# ProxSensorType2_Transmit.net
KiCad netlist of a schematic drawn in Altium Designer
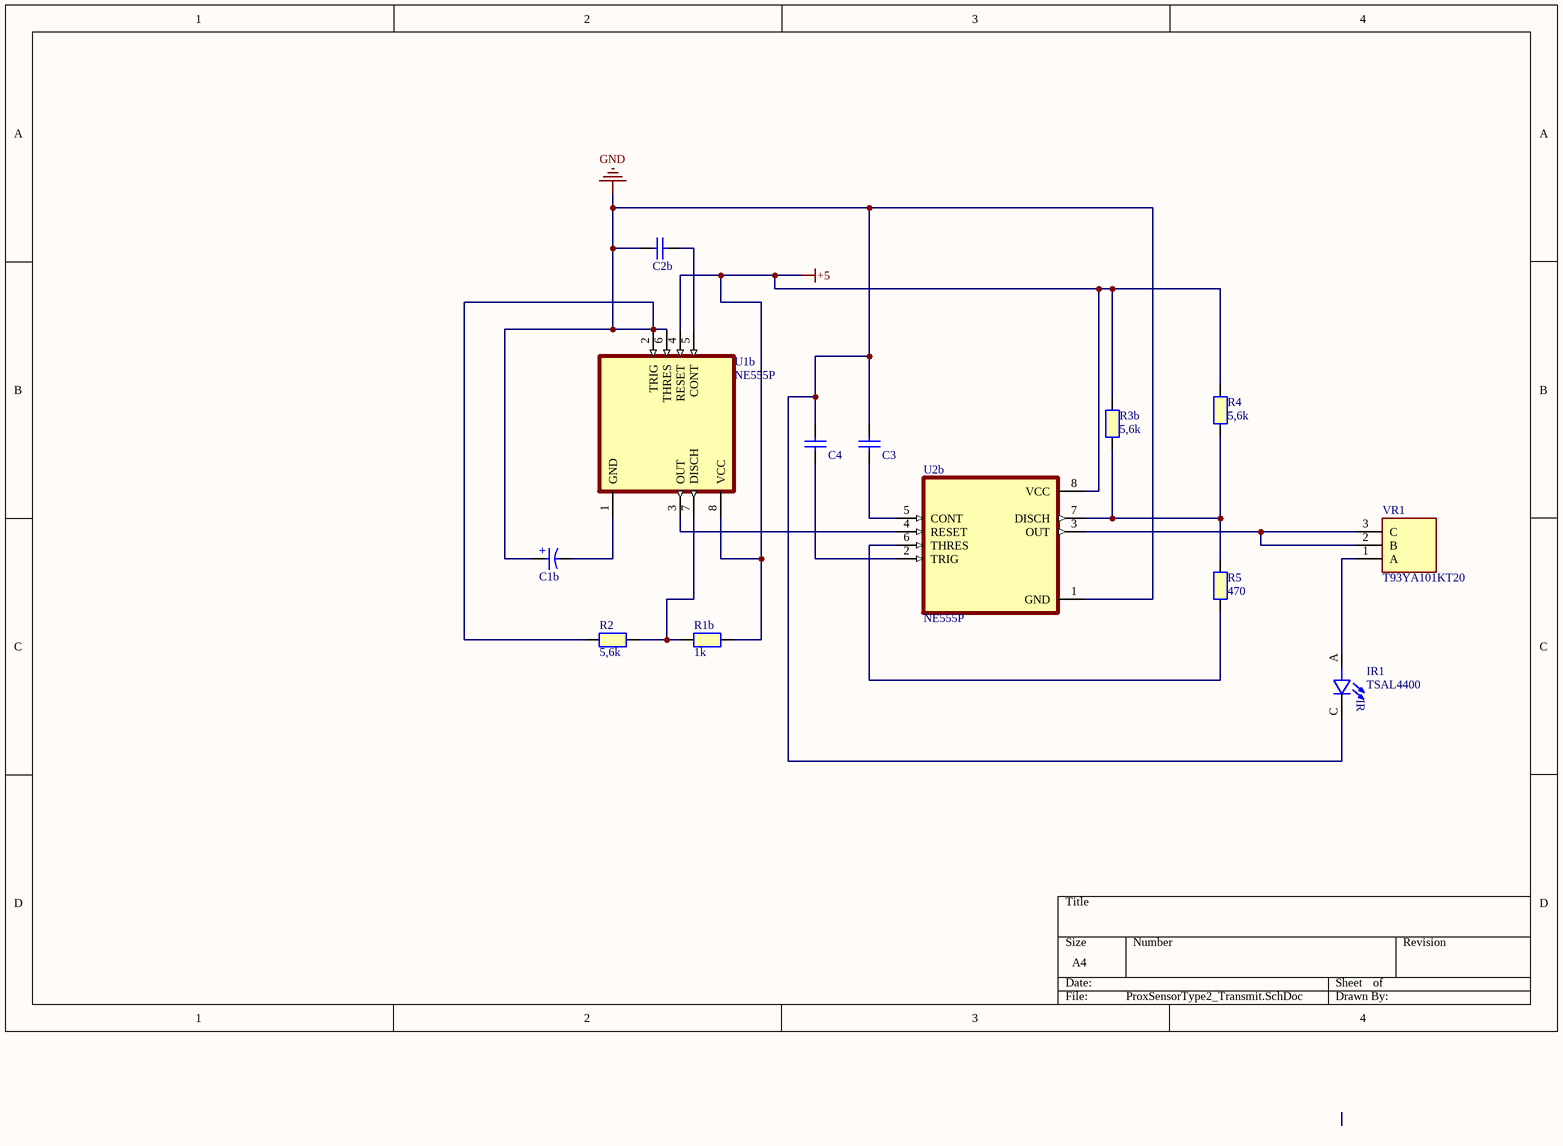
[diagram p0: ProxSensorType2_Transmit.SchDoc]

(export (version "E")
  (design (tool "Eeschema 10.0.6"))
  (components
    (comp (ref "C1b")
      (value "1µF")
      (footprint "WCAP-ATG8_D5H11")
      (description "WCAP-ATG8 Aluminum Electrolytic Capacitor, Radial, THT, D5 x H11mm, 100µF, 10V")
      (fields
        (field (name "MANUFACTURER PART NUMBER") "860010272005")
        (field (name "MANUFACTURER") "Wurth Elektronik")
      )
      (libsource (lib "Sensor_1") (part "860010272005"))
    )
    (comp (ref "C2b")
      (value "0,01uF")
      (footprint "WCAP-CSGP_0805_L2W1.25H0.8_Wave")
      (description "WCAP-CSGP Multilayer Ceramic Chip Capacitor, General Purpose, size 0201, NP0 Class I, 22pF, 25VDC")
      (fields
        (field (name "MANUFACTURER PART NUMBER") "885012004008")
        (field (name "MANUFACTURER") "Wurth Elektronik")
      )
      (libsource (lib "Sensor_1") (part "885012004008"))
    )
    (comp (ref "C3")
      (value "0,01uF")
      (footprint "WCAP-CSGP_0805_L2W1.25H0.8_Wave")
      (description "WCAP-CSGP Multilayer Ceramic Chip Capacitor, General Purpose, size 0201, NP0 Class I, 22pF, 25VDC")
      (fields
        (field (name "MANUFACTURER PART NUMBER") "885012004008")
        (field (name "MANUFACTURER") "Wurth Elektronik")
      )
      (libsource (lib "Sensor_1") (part "885012004008"))
    )
    (comp (ref "C4")
      (value "0,01uF")
      (footprint "WCAP-CSGP_0805_L2W1.25H0.8_Wave")
      (description "WCAP-CSGP Multilayer Ceramic Chip Capacitor, General Purpose, size 0201, NP0 Class I, 22pF, 25VDC")
      (fields
        (field (name "MANUFACTURER PART NUMBER") "885012004008")
        (field (name "MANUFACTURER") "Wurth Elektronik")
      )
      (libsource (lib "Sensor_1") (part "885012004008"))
    )
    (comp (ref "IR1")
      (value "TSAL4400")
      (footprint "Sensor_1:LEDRD254W45D335H610")
      (description "Infrared Emitter 940nm 36mW/sr Circular Top Mount 2-Pin T-1 Bulk")
      (fields (field (name "MF") "Vishay Semiconductor"))
      (libsource (lib "Sensor_1") (part "TSAL4400"))
    )
    (comp (ref "R1b")
      (value "1k")
      (footprint "RESC2012X50N")
      (description "4,7k Resistor 0805")
      (fields (field (name "PART NUMBER") "TNPW080510K0BETA") (field (name "MANUFACTURER") "Vishay Dale"))
      (libsource (lib "") (part "RESISTOR 0805_1"))
    )
    (comp (ref "R2")
      (value "5,6k")
      (footprint "RESC2012X50N")
      (description "4,7k Resistor 0805")
      (fields (field (name "PART NUMBER") "TNPW080510K0BETA") (field (name "MANUFACTURER") "Vishay Dale"))
      (libsource (lib "") (part "RESISTOR 0805_1"))
    )
    (comp (ref "R3b")
      (value "5,6k")
      (footprint "RESC2012X50N")
      (description "4,7k Resistor 0805")
      (fields (field (name "PART NUMBER") "TNPW080510K0BETA") (field (name "MANUFACTURER") "Vishay Dale"))
      (libsource (lib "Sensor_1") (part "RESISTOR 0805"))
    )
    (comp (ref "R4")
      (value "5,6k")
      (footprint "RESC2012X50N")
      (description "4,7k Resistor 0805")
      (fields (field (name "PART NUMBER") "TNPW080510K0BETA") (field (name "MANUFACTURER") "Vishay Dale"))
      (libsource (lib "Sensor_1") (part "RESISTOR 0805"))
    )
    (comp (ref "R5")
      (value "470")
      (footprint "RESC2012X50N")
      (description "4,7k Resistor 0805")
      (fields (field (name "PART NUMBER") "TNPW080510K0BETA") (field (name "MANUFACTURER") "Vishay Dale"))
      (libsource (lib "Sensor_1") (part "RESISTOR 0805"))
    )
    (comp (ref "U1b")
      (value "NE555P")
      (footprint "Sensor_1:DIP794W45P254L959H508Q8")
      (libsource (lib "Sensor_1") (part "NE555P"))
    )
    (comp (ref "U2b")
      (value "NE555P")
      (footprint "Sensor_1:DIP794W45P254L959H508Q8")
      (libsource (lib "") (part "NE555P_1"))
    )
    (comp (ref "VR1")
      (value "T93YA101KT20")
      (footprint "T93YA5K10")
      (description "100, Through Hole Trimmer Potentiometer 0.5W Top Adjust Vishay, T93")
      (fields (field (name "MOUSER PART NUMBER") "72-T93YA-100"))
      (libsource (lib "Sensor_1") (part "T93YA101KT20"))
    )
  )
  (nets
    (net (code "1") (name "+5") (class "Default")
      (node (ref "R1b") (pin "2") (pinfunction "2_2") (pintype "passive"))
      (node (ref "R3b") (pin "2") (pinfunction "2_2") (pintype "passive"))
      (node (ref "R4") (pin "2") (pinfunction "2_2") (pintype "passive"))
      (node (ref "U1b") (pin "4") (pinfunction "RESET_4") (pintype "input"))
      (node (ref "U1b") (pin "8") (pinfunction "VCC_8") (pintype "power_in"))
      (node (ref "U2b") (pin "8") (pinfunction "VCC_8") (pintype "power_in"))
    )
    (net (code "2") (name "GND") (class "Default")
      (node (ref "C1b") (pin "1") (pinfunction "P_1") (pintype "passive"))
      (node (ref "C2b") (pin "1") (pinfunction "1_1") (pintype "passive"))
      (node (ref "C3") (pin "2") (pinfunction "2_2") (pintype "passive"))
      (node (ref "C4") (pin "2") (pinfunction "2_2") (pintype "passive"))
      (node (ref "IR1") (pin "C") (pinfunction "C_C") (pintype "passive"))
      (node (ref "R2") (pin "1") (pinfunction "1_1") (pintype "passive"))
      (node (ref "U1b") (pin "2") (pinfunction "TRIG_2") (pintype "input"))
      (node (ref "U1b") (pin "6") (pinfunction "THRES_6") (pintype "input"))
      (node (ref "U2b") (pin "1") (pinfunction "GND_1") (pintype "power_in"))
    )
    (net (code "3") (name "Net-(C1b-N)") (class "Default")
      (node (ref "C1b") (pin "2") (pinfunction "N_2") (pintype "passive"))
      (node (ref "U1b") (pin "1") (pinfunction "GND_1") (pintype "power_in"))
    )
    (net (code "4") (name "Net-(U1b-CONT)") (class "Default")
      (node (ref "C2b") (pin "2") (pinfunction "2_2") (pintype "passive"))
      (node (ref "U1b") (pin "5") (pinfunction "CONT_5") (pintype "input"))
    )
    (net (code "5") (name "Net-(U1b-DISCH)") (class "Default")
      (node (ref "R1b") (pin "1") (pinfunction "1_1") (pintype "passive"))
      (node (ref "R2") (pin "2") (pinfunction "2_2") (pintype "passive"))
      (node (ref "U1b") (pin "7") (pinfunction "DISCH_7") (pintype "output"))
    )
    (net (code "6") (name "Net-(U1b-OUT)") (class "Default")
      (node (ref "U1b") (pin "3") (pinfunction "OUT_3") (pintype "output"))
      (node (ref "U2b") (pin "4") (pinfunction "RESET_4") (pintype "input"))
    )
    (net (code "7") (name "Net-(U2b-CONT)") (class "Default")
      (node (ref "C3") (pin "1") (pinfunction "1_1") (pintype "passive"))
      (node (ref "U2b") (pin "5") (pinfunction "CONT_5") (pintype "input"))
    )
    (net (code "8") (name "Net-(U2b-DISCH)") (class "Default")
      (node (ref "R3b") (pin "1") (pinfunction "1_1") (pintype "passive"))
      (node (ref "R4") (pin "1") (pinfunction "1_1") (pintype "passive"))
      (node (ref "R5") (pin "2") (pinfunction "2_2") (pintype "passive"))
      (node (ref "U2b") (pin "7") (pinfunction "DISCH_7") (pintype "output"))
    )
    (net (code "9") (name "Net-(U2b-OUT)") (class "Default")
      (node (ref "U2b") (pin "3") (pinfunction "OUT_3") (pintype "output"))
      (node (ref "VR1") (pin "2") (pinfunction "B_2") (pintype "passive"))
      (node (ref "VR1") (pin "3") (pinfunction "C_3") (pintype "passive"))
    )
    (net (code "10") (name "Net-(U2b-THRES)") (class "Default")
      (node (ref "R5") (pin "1") (pinfunction "1_1") (pintype "passive"))
      (node (ref "U2b") (pin "6") (pinfunction "THRES_6") (pintype "input"))
    )
    (net (code "11") (name "Net-(U2b-TRIG)") (class "Default")
      (node (ref "C4") (pin "1") (pinfunction "1_1") (pintype "passive"))
      (node (ref "U2b") (pin "2") (pinfunction "TRIG_2") (pintype "input"))
    )
    (net (code "12") (name "Net-(VR1-A)") (class "Default")
      (node (ref "IR1") (pin "A") (pinfunction "A_A") (pintype "passive"))
      (node (ref "VR1") (pin "1") (pinfunction "A_1") (pintype "passive"))
    )
  )
)
